# Safety_Loop.net
KiCad netlist of a schematic drawn in Altium Designer
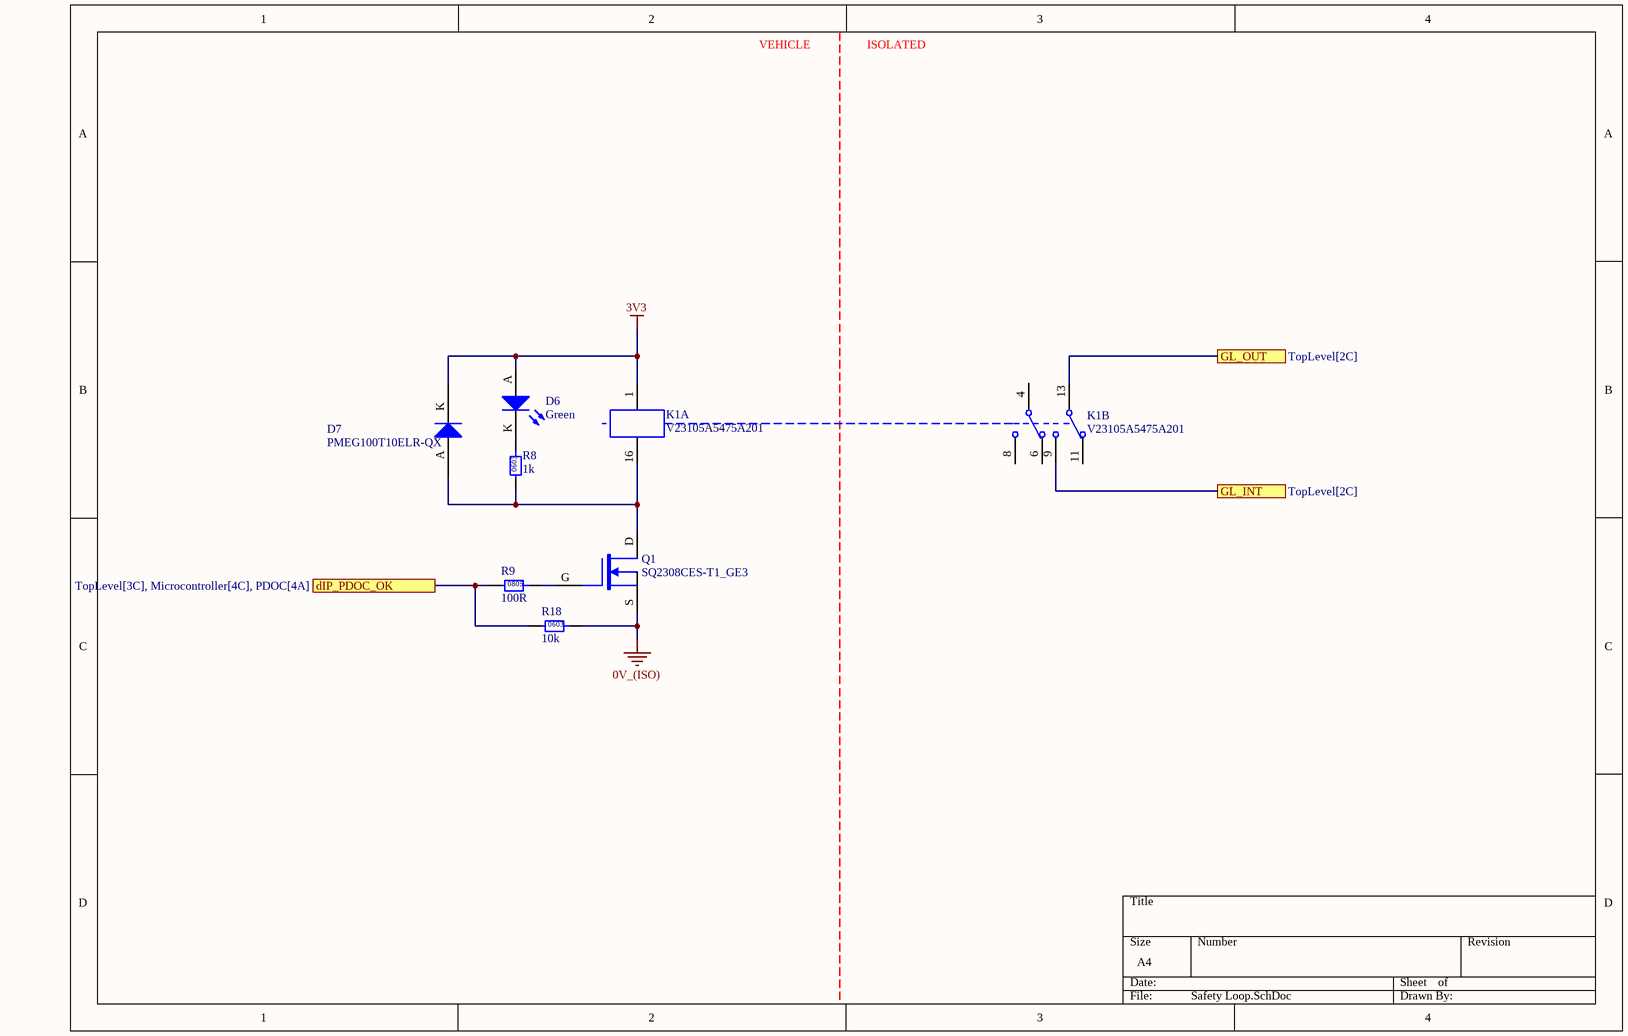
[diagram p0: Safety Loop.SchDoc]

(export (version "E")
  (design (tool "Eeschema 10.0.6"))
  (components
    (comp (ref "D6")
      (value "Green")
      (footprint "0805 LED")
      (description "Green LED Indication - Discrete 1.75V 0805 (2012 Metric)")
      (fields (field (name "PART NUMBER") "SML-210FTT86") (field (name "MANUFACTURER") "ROHM Semiconductor"))
      (libsource (lib "ts_standard_library") (part "LED"))
    )
    (comp (ref "D7")
      (value "PMEG100T10ELR-QX")
      (footprint "SODFL350X110-2N")
      (description "Diode 100 V 1A Surface Mount SOD-123W")
      (libsource (lib "Team Swinburne") (part "PMEG100T10ELR-QX"))
    )
    (comp (ref "K1")
      (value "V23105A5475A201")
      (footprint "TI 2-DIL")
      (description "5V DPDT Relay 3A 220VDC")
      (libsource (lib "") (part "Symbol_1"))
    )
    (comp (ref "Q1")
      (value "SQ2308CES-T1_GE3")
      (footprint "VSHY SOT-23-3")
      (description "MOSFET N-CH 60V 2.3A SOT23")
      (fields
        (field (name "MANUFACTURER") "Vishay Siliconix")
        (field (name "DIGIKEY PART NUMBER") "SQ2308CES-T1_GE3CT-ND")
        (field (name "PUBLISHER") "Altium Limited")
      )
      (libsource (lib "ts_standard_library") (part "MOSFET-N"))
    )
    (comp (ref "R8")
      (value "1k")
      (footprint "0603")
      (fields
        (field (name "PART NUMBER") "RC0603FR-071KL")
        (field (name "MANUFACTURER") "YAGEO")
        (field (name "TOLERANCE") "0.01")
      )
      (libsource (lib "ts_standard_library") (part "Resistor 0603"))
    )
    (comp (ref "R9")
      (value "100R")
      (footprint "0805")
      (fields
        (field (name "PART NUMBER") "RC0805FR07100RL")
        (field (name "MANUFACTURER") "YAGEO")
        (field (name "TOLERANCE") "0.01")
      )
      (libsource (lib "ts_standard_library") (part "Resistor 0805"))
    )
    (comp (ref "R18")
      (value "10k")
      (footprint "0603")
      (fields
        (field (name "PART NUMBER") "RC0603FR-0710KL")
        (field (name "MANUFACTURER") "YAGEO")
        (field (name "TOLERANCE") "0.01")
      )
      (libsource (lib "ts_standard_library") (part "Resistor 0603"))
    )
  )
  (nets
    (net (code "1") (name "/GL_INT") (class "Default")
      (node (ref "K1") (pin "9") (pinfunction "9_9") (pintype "passive"))
    )
    (net (code "2") (name "/GL_OUT") (class "Default")
      (node (ref "K1") (pin "13") (pinfunction "13_13") (pintype "passive"))
    )
    (net (code "3") (name "/dIP_PDOC_OK") (class "Default")
      (node (ref "R18") (pin "1") (pinfunction "1_1") (pintype "passive"))
      (node (ref "R9") (pin "1") (pinfunction "1_1") (pintype "passive"))
    )
    (net (code "4") (name "0V_(ISO)") (class "Default")
      (node (ref "Q1") (pin "S") (pinfunction "S_S") (pintype "passive"))
      (node (ref "R18") (pin "2") (pinfunction "2_2") (pintype "passive"))
    )
    (net (code "5") (name "3V3") (class "Default")
      (node (ref "D6") (pin "A") (pinfunction "A_A") (pintype "passive"))
      (node (ref "D7") (pin "K") (pintype "passive"))
      (node (ref "K1") (pin "1") (pinfunction "1_1") (pintype "passive"))
    )
    (net (code "6") (name "Net-(D6-PadK)") (class "Default")
      (node (ref "D6") (pin "K") (pinfunction "K_K") (pintype "passive"))
      (node (ref "R8") (pin "2") (pinfunction "2_2") (pintype "passive"))
    )
    (net (code "7") (name "Net-(D7-PadA)") (class "Default")
      (node (ref "D7") (pin "A") (pintype "passive"))
      (node (ref "K1") (pin "16") (pinfunction "16_16") (pintype "passive"))
      (node (ref "Q1") (pin "D") (pinfunction "D_D") (pintype "passive"))
      (node (ref "R8") (pin "1") (pinfunction "1_1") (pintype "passive"))
    )
    (net (code "8") (name "Net-(Q1-PadG)") (class "Default")
      (node (ref "Q1") (pin "G") (pinfunction "G_G") (pintype "passive"))
      (node (ref "R9") (pin "2") (pinfunction "2_2") (pintype "passive"))
    )
    (net (code "9") (name "unconnected-(K1-Pad4)") (class "Default")
      (node (ref "K1") (pin "4") (pinfunction "4_4") (pintype "passive"))
    )
    (net (code "10") (name "unconnected-(K1-Pad6)") (class "Default")
      (node (ref "K1") (pin "6") (pinfunction "6_6") (pintype "passive"))
    )
    (net (code "11") (name "unconnected-(K1-Pad8)") (class "Default")
      (node (ref "K1") (pin "8") (pinfunction "8_8") (pintype "passive"))
    )
    (net (code "12") (name "unconnected-(K1-Pad11)") (class "Default")
      (node (ref "K1") (pin "11") (pinfunction "11_11") (pintype "passive"))
    )
  )
)
